# Powerboard_schematic_overlay_3_19_2018.net
KiCad netlist of a schematic drawn in Altium Designer
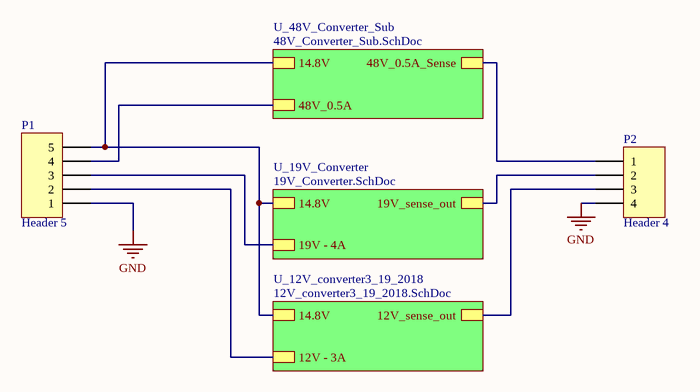
[diagram p0: Powerboard_schematic_overlay_3_19_2018.SchDoc]

(export (version "E")
  (design (tool "Eeschema 10.0.6"))
  (components
    (comp (ref "P1")
      (value "Header 5")
      (footprint "HDR1X5")
      (description "Header, 5-Pin")
      (fields (field (name "PUBLISHER") "Altium Limited"))
      (libsource (lib "Miscellaneous Connectors") (part "Header 5"))
    )
    (comp (ref "P2")
      (value "Header 4")
      (footprint "HDR1X4")
      (description "Header, 4-Pin")
      (fields (field (name "PUBLISHER") "Altium Limited"))
      (libsource (lib "Miscellaneous Connectors") (part "Header 4"))
    )
  )
  (nets
    (net (code "1") (name "/12V - 3A") (class "Default")
      (node (ref "P1") (pin "2") (pinfunction "2_2") (pintype "passive"))
    )
    (net (code "2") (name "/12V_sense_out") (class "Default")
      (node (ref "P2") (pin "3") (pinfunction "3_3") (pintype "passive"))
    )
    (net (code "3") (name "/14.8V") (class "Default")
      (node (ref "P1") (pin "5") (pinfunction "5_5") (pintype "passive"))
    )
    (net (code "4") (name "/19V - 4A") (class "Default")
      (node (ref "P1") (pin "3") (pinfunction "3_3") (pintype "passive"))
    )
    (net (code "5") (name "/19V_sense_out") (class "Default")
      (node (ref "P2") (pin "2") (pinfunction "2_2") (pintype "passive"))
    )
    (net (code "6") (name "/48V_0.5A") (class "Default")
      (node (ref "P1") (pin "4") (pinfunction "4_4") (pintype "passive"))
    )
    (net (code "7") (name "/48V_0.5A_Sense") (class "Default")
      (node (ref "P2") (pin "1") (pinfunction "1_1") (pintype "passive"))
    )
    (net (code "8") (name "GND") (class "Default")
      (node (ref "P1") (pin "1") (pinfunction "1_1") (pintype "passive"))
      (node (ref "P2") (pin "4") (pinfunction "4_4") (pintype "passive"))
    )
  )
)
